# neojoint2-090.net
KiCad netlist of a schematic drawn in EAGLE
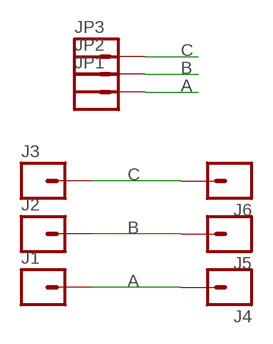
[diagram p0: schematic, sheet 1]

(export (version "E")
  (design (tool "Eeschema 10.0.6"))
  (components
    (comp (ref "J1")
      (value "M01SMD-4.5X1.5")
      (footprint "eagle-import:PAD-1.5X4.5")
      (libsource (lib "eagle-import") (part "M01SMD-4.5X1.5"))
    )
    (comp (ref "J2")
      (value "M01SMD-4.5X1.5")
      (footprint "eagle-import:PAD-1.5X4.5")
      (libsource (lib "eagle-import") (part "M01SMD-4.5X1.5"))
    )
    (comp (ref "J3")
      (value "M01SMD-4.5X1.5")
      (footprint "eagle-import:PAD-1.5X4.5")
      (libsource (lib "eagle-import") (part "M01SMD-4.5X1.5"))
    )
    (comp (ref "J4")
      (value "M01SMD-4.5X1.5")
      (footprint "eagle-import:PAD-1.5X4.5")
      (libsource (lib "eagle-import") (part "M01SMD-4.5X1.5"))
    )
    (comp (ref "J5")
      (value "M01SMD-4.5X1.5")
      (footprint "eagle-import:PAD-1.5X4.5")
      (libsource (lib "eagle-import") (part "M01SMD-4.5X1.5"))
    )
    (comp (ref "J6")
      (value "M01SMD-4.5X1.5")
      (footprint "eagle-import:PAD-1.5X4.5")
      (libsource (lib "eagle-import") (part "M01SMD-4.5X1.5"))
    )
    (comp (ref "JP1")
      (value "M01PTH")
      (footprint "eagle-import:1X01")
      (libsource (lib "eagle-import") (part "M01PTH"))
    )
    (comp (ref "JP2")
      (value "M01PTH")
      (footprint "eagle-import:1X01")
      (libsource (lib "eagle-import") (part "M01PTH"))
    )
    (comp (ref "JP3")
      (value "M01PTH")
      (footprint "eagle-import:1X01")
      (libsource (lib "eagle-import") (part "M01PTH"))
    )
  )
  (nets
    (net (code "1") (name "/A") (class "Default")
      (node (ref "J1") (pin "P$1") (pinfunction "1_P$1") (pintype "passive"))
      (node (ref "J4") (pin "P$1") (pinfunction "1_P$1") (pintype "passive"))
      (node (ref "JP1") (pin "1") (pinfunction "1_1") (pintype "passive"))
    )
    (net (code "2") (name "/B") (class "Default")
      (node (ref "J2") (pin "P$1") (pinfunction "1_P$1") (pintype "passive"))
      (node (ref "J5") (pin "P$1") (pinfunction "1_P$1") (pintype "passive"))
      (node (ref "JP2") (pin "1") (pinfunction "1_1") (pintype "passive"))
    )
    (net (code "3") (name "/C") (class "Default")
      (node (ref "J3") (pin "P$1") (pinfunction "1_P$1") (pintype "passive"))
      (node (ref "J6") (pin "P$1") (pinfunction "1_P$1") (pintype "passive"))
      (node (ref "JP3") (pin "1") (pinfunction "1_1") (pintype "passive"))
    )
  )
)
